# LED_with_Regulator.net
KiCad netlist of a schematic drawn in EAGLE
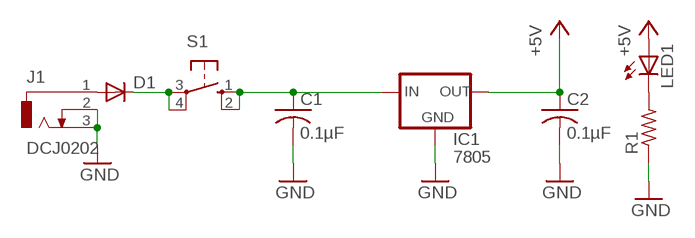
[diagram p0: schematic, sheet 1]

(export (version "E")
  (design (tool "Eeschema 10.0.6"))
  (components
    (comp (ref "C1")
      (value "0.1µF")
      (footprint "eagle-import:C025-025X050")
      (libsource (lib "eagle-import") (part "C-US025-025X050"))
    )
    (comp (ref "C2")
      (value "0.1µF")
      (footprint "eagle-import:C025-025X050")
      (libsource (lib "eagle-import") (part "C-US025-025X050"))
    )
    (comp (ref "D1")
      (value "DIODE-D-7.5")
      (footprint "eagle-import:D-7.5")
      (libsource (lib "eagle-import") (part "DIODE-D-7.5"))
    )
    (comp (ref "IC1")
      (value "7805")
      (footprint "eagle-import:78XXL")
      (libsource (lib "eagle-import") (part "78XXL"))
    )
    (comp (ref "J1")
      (value "DCJ0202")
      (footprint "eagle-import:DCJ0202")
      (libsource (lib "eagle-import") (part "DCJ0202"))
    )
    (comp (ref "LED1")
      (value "LED5MM")
      (footprint "eagle-import:LED5MM")
      (libsource (lib "eagle-import") (part "LED5MM"))
    )
    (comp (ref "R1")
      (value "R-US_0204/5")
      (footprint "eagle-import:0204_5")
      (libsource (lib "eagle-import") (part "R-US_0204/5"))
    )
    (comp (ref "S1")
      (value "10-XX")
      (footprint "eagle-import:B3F-10XX")
      (fields (field (name "MPN") "B3F-1000"))
      (libsource (lib "eagle-import") (part "10-XX"))
    )
  )
  (nets
    (net (code "1") (name "+5V") (class "Default")
      (node (ref "C2") (pin "1") (pinfunction "1_1") (pintype "passive"))
      (node (ref "IC1") (pin "OUT") (pinfunction "OUT_OUT") (pintype "passive"))
      (node (ref "LED1") (pin "A") (pinfunction "A_A") (pintype "passive"))
    )
    (net (code "2") (name "GND") (class "Default")
      (node (ref "C1") (pin "2") (pinfunction "2_2") (pintype "passive"))
      (node (ref "C2") (pin "2") (pinfunction "2_2") (pintype "passive"))
      (node (ref "IC1") (pin "GND") (pinfunction "GND_GND") (pintype "input"))
      (node (ref "J1") (pin "2") (pinfunction "2_2") (pintype "passive"))
      (node (ref "J1") (pin "3") (pinfunction "3_3") (pintype "passive"))
      (node (ref "R1") (pin "1") (pinfunction "1_1") (pintype "passive"))
    )
    (net (code "3") (name "Net-(D1-PadA)") (class "Default")
      (node (ref "D1") (pin "A") (pinfunction "A_A") (pintype "passive"))
      (node (ref "J1") (pin "1") (pinfunction "1_1") (pintype "passive"))
    )
    (net (code "4") (name "Net-(LED1-C)") (class "Default")
      (node (ref "LED1") (pin "K") (pinfunction "C_K") (pintype "passive"))
      (node (ref "R1") (pin "2") (pinfunction "2_2") (pintype "passive"))
    )
    (net (code "5") (name "Net-(S1-P)") (class "Default")
      (node (ref "D1") (pin "C") (pinfunction "C_C") (pintype "passive"))
      (node (ref "S1") (pin "3") (pinfunction "P_3") (pintype "passive"))
      (node (ref "S1") (pin "4") (pinfunction "P1_4") (pintype "passive"))
    )
    (net (code "6") (name "Net-(S1-S)") (class "Default")
      (node (ref "C1") (pin "1") (pinfunction "1_1") (pintype "passive"))
      (node (ref "IC1") (pin "IN") (pinfunction "IN_IN") (pintype "input"))
      (node (ref "S1") (pin "1") (pinfunction "S_1") (pintype "passive"))
      (node (ref "S1") (pin "2") (pinfunction "S1_2") (pintype "passive"))
    )
  )
)
